# JoyStick_SCH.net
KiCad netlist of a schematic drawn in Altium Designer
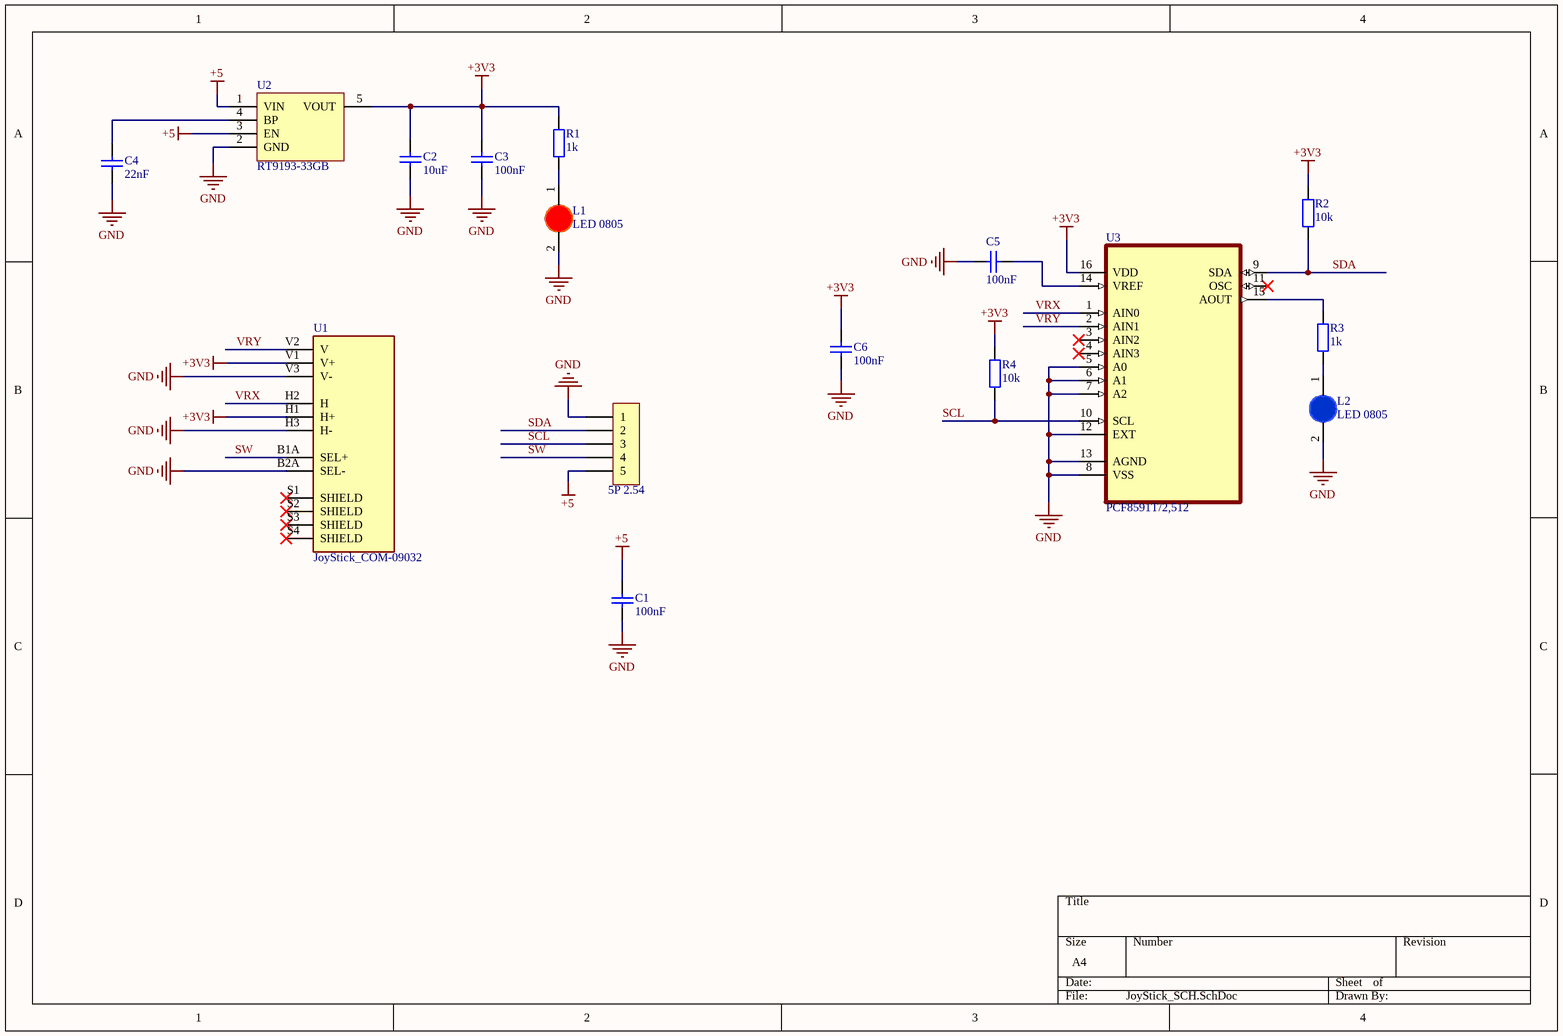
[diagram p0: JoyStick_SCH.SchDoc]

(export (version "E")
  (design (tool "Eeschema 10.0.6"))
  (components
    (comp (ref "C1")
      (value "100nF")
      (footprint "tu 0603")
      (description "Dán")
      (libsource (lib "namnt_Lib") (part "Tu 0603 104 50V 10%"))
    )
    (comp (ref "C2")
      (value "10uF")
      (footprint "tu 0603")
      (description "Dán")
      (libsource (lib "namnt_Lib") (part "Tu 0603 106 16V 20%"))
    )
    (comp (ref "C3")
      (value "100nF")
      (footprint "tu 0603")
      (description "Dán")
      (libsource (lib "namnt_Lib") (part "Tu 0603 104 50V 10%"))
    )
    (comp (ref "C4")
      (value "22nF")
      (footprint "tu 0603")
      (description "Dán")
      (libsource (lib "namnt_Lib") (part "Tu 0603 104 50V 10%"))
    )
    (comp (ref "C5")
      (value "100nF")
      (footprint "tu 0603")
      (description "Dán")
      (libsource (lib "namnt_Lib") (part "Tu 0603 104 50V 10%"))
    )
    (comp (ref "C6")
      (value "100nF")
      (footprint "tu 0603")
      (description "Dán")
      (libsource (lib "namnt_Lib") (part "Tu 0603 104 50V 10%"))
    )
    (comp (ref "H1")
      (value "5P 2.54")
      (footprint "Header 5P DC 2.54")
      (description "Cắm")
      (libsource (lib "namnt_Lib") (part "Header 5P 2.54 Duc Cong"))
    )
    (comp (ref "L1")
      (value "LED 0805")
      (footprint "LED-0805-Red")
      (description "Dán")
      (libsource (lib "namnt_Lib") (part "LED 0805 Do"))
    )
    (comp (ref "L2")
      (value "LED 0805")
      (footprint "LED-0805-Blue")
      (description "Dán")
      (libsource (lib "namnt_Lib") (part "LED 0805 Xanh Duong"))
    )
    (comp (ref "R1")
      (value "1k")
      (footprint "tro smd 0603")
      (description "Dán")
      (libsource (lib "namnt_Lib") (part "Tro 0603 1% 1k"))
    )
    (comp (ref "R2")
      (value "10k")
      (footprint "tro smd 0603")
      (description "Dán")
      (libsource (lib "namnt_Lib") (part "Tro 0603 1% 10k"))
    )
    (comp (ref "R3")
      (value "1k")
      (footprint "tro smd 0603")
      (description "Dán")
      (libsource (lib "namnt_Lib") (part "Tro 0603 1% 1k"))
    )
    (comp (ref "R4")
      (value "10k")
      (footprint "tro smd 0603")
      (description "Dán")
      (libsource (lib "namnt_Lib") (part "Tro 0603 1% 10k"))
    )
    (comp (ref "U1")
      (value "JoyStick_COM-09032")
      (footprint "XDCR_COM-09032")
      (description "Thumb Joystick")
      (fields (field (name "MP") "COM-09032"))
      (libsource (lib "namnt_Lib") (part "JoyStick_COM-09032"))
    )
    (comp (ref "U2")
      (value "RT9193-33GB")
      (footprint "SOT23-5")
      (description "Linear Voltage Regulator IC 1 Output 300mA SOT-23-5")
      (fields (field (name "MANUFACTURER") "Richtek USA Inc."))
      (libsource (lib "namnt_Lib") (part "REG_5.5V-3.3V-0.3A-1W-SOT-23-5"))
    )
    (comp (ref "U3")
      (value "PCF8591T/2,512")
      (footprint "SOIC127P1032X265-16N")
      (description "ADC, DAC 8 b 11.1k I2C, Serial 16-SO")
      (fields (field (name "MF") "NXP USA"))
      (libsource (lib "namnt_Lib") (part "PCF8591T/2,512"))
    )
  )
  (nets
    (net (code "1") (name "+3V3") (class "Default")
      (node (ref "C2") (pin "1") (pinfunction "1_1") (pintype "passive"))
      (node (ref "C3") (pin "1") (pinfunction "1_1") (pintype "passive"))
      (node (ref "C6") (pin "1") (pinfunction "1_1") (pintype "passive"))
      (node (ref "R1") (pin "2") (pinfunction "2_2") (pintype "passive"))
      (node (ref "R2") (pin "2") (pinfunction "2_2") (pintype "passive"))
      (node (ref "R4") (pin "2") (pinfunction "2_2") (pintype "passive"))
      (node (ref "U1") (pin "H1") (pinfunction "H+_H1") (pintype "passive"))
      (node (ref "U1") (pin "V1") (pinfunction "V+_V1") (pintype "passive"))
      (node (ref "U2") (pin "5") (pinfunction "VOUT_5") (pintype "passive"))
      (node (ref "U3") (pin "16") (pinfunction "VDD_16") (pintype "power_in"))
    )
    (net (code "2") (name "+5") (class "Default")
      (node (ref "C1") (pin "1") (pinfunction "1_1") (pintype "passive"))
      (node (ref "H1") (pin "5") (pinfunction "5_5") (pintype "passive"))
      (node (ref "U2") (pin "1") (pinfunction "VIN_1") (pintype "passive"))
      (node (ref "U2") (pin "3") (pinfunction "EN_3") (pintype "passive"))
    )
    (net (code "3") (name "/SCL") (class "Default")
      (node (ref "H1") (pin "3") (pinfunction "3_3") (pintype "passive"))
      (node (ref "R4") (pin "1") (pinfunction "1_1") (pintype "passive"))
      (node (ref "U3") (pin "10") (pinfunction "SCL_10") (pintype "input"))
    )
    (net (code "4") (name "/SDA") (class "Default")
      (node (ref "H1") (pin "2") (pinfunction "2_2") (pintype "passive"))
      (node (ref "R2") (pin "1") (pinfunction "1_1") (pintype "passive"))
      (node (ref "U3") (pin "9") (pinfunction "SDA_9") (pintype "bidirectional"))
    )
    (net (code "5") (name "/SW") (class "Default")
      (node (ref "H1") (pin "4") (pinfunction "4_4") (pintype "passive"))
      (node (ref "U1") (pin "B1A") (pinfunction "SEL+_B1A") (pintype "passive"))
    )
    (net (code "6") (name "/VRX") (class "Default")
      (node (ref "U1") (pin "H2") (pinfunction "H_H2") (pintype "passive"))
      (node (ref "U3") (pin "1") (pinfunction "AIN0_1") (pintype "input"))
    )
    (net (code "7") (name "/VRY") (class "Default")
      (node (ref "U1") (pin "V2") (pinfunction "V_V2") (pintype "passive"))
      (node (ref "U3") (pin "2") (pinfunction "AIN1_2") (pintype "input"))
    )
    (net (code "8") (name "GND") (class "Default")
      (node (ref "C1") (pin "2") (pinfunction "2_2") (pintype "passive"))
      (node (ref "C2") (pin "2") (pinfunction "2_2") (pintype "passive"))
      (node (ref "C3") (pin "2") (pinfunction "2_2") (pintype "passive"))
      (node (ref "C4") (pin "2") (pinfunction "2_2") (pintype "passive"))
      (node (ref "C5") (pin "2") (pinfunction "2_2") (pintype "passive"))
      (node (ref "C6") (pin "2") (pinfunction "2_2") (pintype "passive"))
      (node (ref "H1") (pin "1") (pinfunction "1_1") (pintype "passive"))
      (node (ref "L1") (pin "2") (pinfunction "K_2") (pintype "passive"))
      (node (ref "L2") (pin "2") (pinfunction "K_2") (pintype "passive"))
      (node (ref "U1") (pin "B2A") (pinfunction "SEL-_B2A") (pintype "passive"))
      (node (ref "U1") (pin "H3") (pinfunction "H-_H3") (pintype "passive"))
      (node (ref "U1") (pin "V3") (pinfunction "V-_V3") (pintype "passive"))
      (node (ref "U2") (pin "2") (pinfunction "GND_2") (pintype "passive"))
      (node (ref "U3") (pin "12") (pinfunction "EXT_12") (pintype "passive"))
      (node (ref "U3") (pin "13") (pinfunction "AGND_13") (pintype "passive"))
      (node (ref "U3") (pin "5") (pinfunction "A0_5") (pintype "input"))
      (node (ref "U3") (pin "6") (pinfunction "A1_6") (pintype "input"))
      (node (ref "U3") (pin "7") (pinfunction "A2_7") (pintype "input"))
      (node (ref "U3") (pin "8") (pinfunction "VSS_8") (pintype "power_in"))
    )
    (net (code "9") (name "Net-(L1-A)") (class "Default")
      (node (ref "L1") (pin "1") (pinfunction "A_1") (pintype "passive"))
      (node (ref "R1") (pin "1") (pinfunction "1_1") (pintype "passive"))
    )
    (net (code "10") (name "Net-(L2-A)") (class "Default")
      (node (ref "L2") (pin "1") (pinfunction "A_1") (pintype "passive"))
      (node (ref "R3") (pin "1") (pinfunction "1_1") (pintype "passive"))
    )
    (net (code "11") (name "Net-(U2-BP)") (class "Default")
      (node (ref "C4") (pin "1") (pinfunction "1_1") (pintype "passive"))
      (node (ref "U2") (pin "4") (pinfunction "BP_4") (pintype "passive"))
    )
    (net (code "12") (name "Net-(U3-AOUT)") (class "Default")
      (node (ref "R3") (pin "2") (pinfunction "2_2") (pintype "passive"))
      (node (ref "U3") (pin "15") (pinfunction "AOUT_15") (pintype "output"))
    )
    (net (code "13") (name "Net-(U3-VREF)") (class "Default")
      (node (ref "C5") (pin "1") (pinfunction "1_1") (pintype "passive"))
      (node (ref "U3") (pin "14") (pinfunction "VREF_14") (pintype "input"))
    )
    (net (code "14") (name "unconnected-(U1-SHIELD-PadS1)") (class "Default")
      (node (ref "U1") (pin "S1") (pinfunction "SHIELD_S1") (pintype "passive+no_connect"))
    )
    (net (code "15") (name "unconnected-(U1-SHIELD-PadS2)") (class "Default")
      (node (ref "U1") (pin "S2") (pinfunction "SHIELD_S2") (pintype "passive+no_connect"))
    )
    (net (code "16") (name "unconnected-(U1-SHIELD-PadS3)") (class "Default")
      (node (ref "U1") (pin "S3") (pinfunction "SHIELD_S3") (pintype "passive+no_connect"))
    )
    (net (code "17") (name "unconnected-(U1-SHIELD-PadS4)") (class "Default")
      (node (ref "U1") (pin "S4") (pinfunction "SHIELD_S4") (pintype "passive+no_connect"))
    )
    (net (code "18") (name "unconnected-(U3-AIN2-Pad3)") (class "Default")
      (node (ref "U3") (pin "3") (pinfunction "AIN2_3") (pintype "input+no_connect"))
    )
    (net (code "19") (name "unconnected-(U3-AIN3-Pad4)") (class "Default")
      (node (ref "U3") (pin "4") (pinfunction "AIN3_4") (pintype "input+no_connect"))
    )
    (net (code "20") (name "unconnected-(U3-OSC-Pad11)") (class "Default")
      (node (ref "U3") (pin "11") (pinfunction "OSC_11") (pintype "bidirectional+no_connect"))
    )
  )
)
